# PowerMCU.net
KiCad netlist of a schematic drawn in Altium Designer
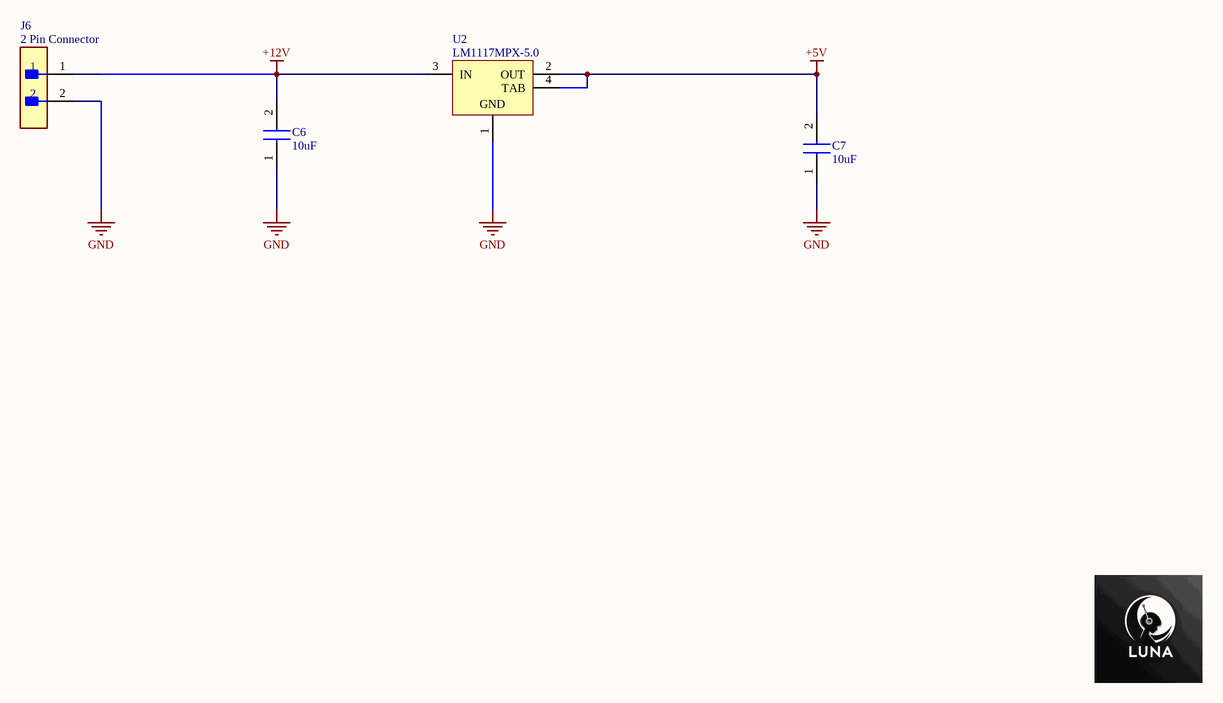
[diagram p0: PowerMCU.SchDoc]

(export (version "E")
  (design (tool "Eeschema 10.0.6"))
  (components
    (comp (ref "C6")
      (value "10uF")
      (footprint "SamacSys:CAPC1608X90N")
      (description "CL10A106KP8NNNC Capacitor")
      (fields
        (field (name "MANUFACTURER_PART_NUMBER") "CL10A106KP8NNNC")
        (field (name "MOUSER PART NUMBER") "187-CL10A106KP8NNNC")
      )
      (libsource (lib "*") (part "CL10A106KP8NNNC"))
    )
    (comp (ref "C7")
      (value "10uF")
      (footprint "SamacSys:CAPC1608X90N")
      (description "CL10A106KP8NNNC Capacitor")
      (fields
        (field (name "MANUFACTURER_PART_NUMBER") "CL10A106KP8NNNC")
        (field (name "MOUSER PART NUMBER") "187-CL10A106KP8NNNC")
      )
      (libsource (lib "*") (part "CL10A106KP8NNNC"))
    )
    (comp (ref "J6")
      (value "2 Pin Connector")
      (footprint "FP-B2B-XH-AM_LF_SN-MFG")
      (description "CONN HEADER VERT 2POS 2.5MM")
      (libsource (lib "Altium Content Vault") (part "3bc925449376181038e59eaffc5286c"))
    )
    (comp (ref "U2")
      (value "LM1117MPX-5.0")
      (footprint "DCY0004A_L")
      (description "800mA Low-Dropout Linear Regulator, 4-pin SOT-223")
      (fields (field (name "MANUFACTURER") "Texas Instruments"))
      (libsource (lib "Altium Content Vault") (part "PM-REG-LM1086-SOT4"))
    )
  )
  (nets
    (net (code "1") (name "+5V") (class "Default")
      (node (ref "C7") (pin "2") (pinfunction "2_2") (pintype "passive"))
      (node (ref "U2") (pin "2") (pinfunction "OUT_2") (pintype "power_in"))
      (node (ref "U2") (pin "4") (pinfunction "TAB_4") (pintype "power_in"))
    )
    (net (code "2") (name "+12V") (class "Default")
      (node (ref "C6") (pin "2") (pinfunction "2_2") (pintype "passive"))
      (node (ref "J6") (pin "1") (pinfunction "1_1") (pintype "passive"))
      (node (ref "U2") (pin "3") (pinfunction "IN_3") (pintype "power_in"))
    )
    (net (code "3") (name "GND") (class "Default")
      (node (ref "C6") (pin "1") (pinfunction "1_1") (pintype "passive"))
      (node (ref "C7") (pin "1") (pinfunction "1_1") (pintype "passive"))
      (node (ref "J6") (pin "2") (pinfunction "2_2") (pintype "passive"))
      (node (ref "U2") (pin "1") (pinfunction "GND_1") (pintype "power_in"))
    )
  )
)
